# Moteino_Leo.net
KiCad netlist of a schematic drawn in EAGLE
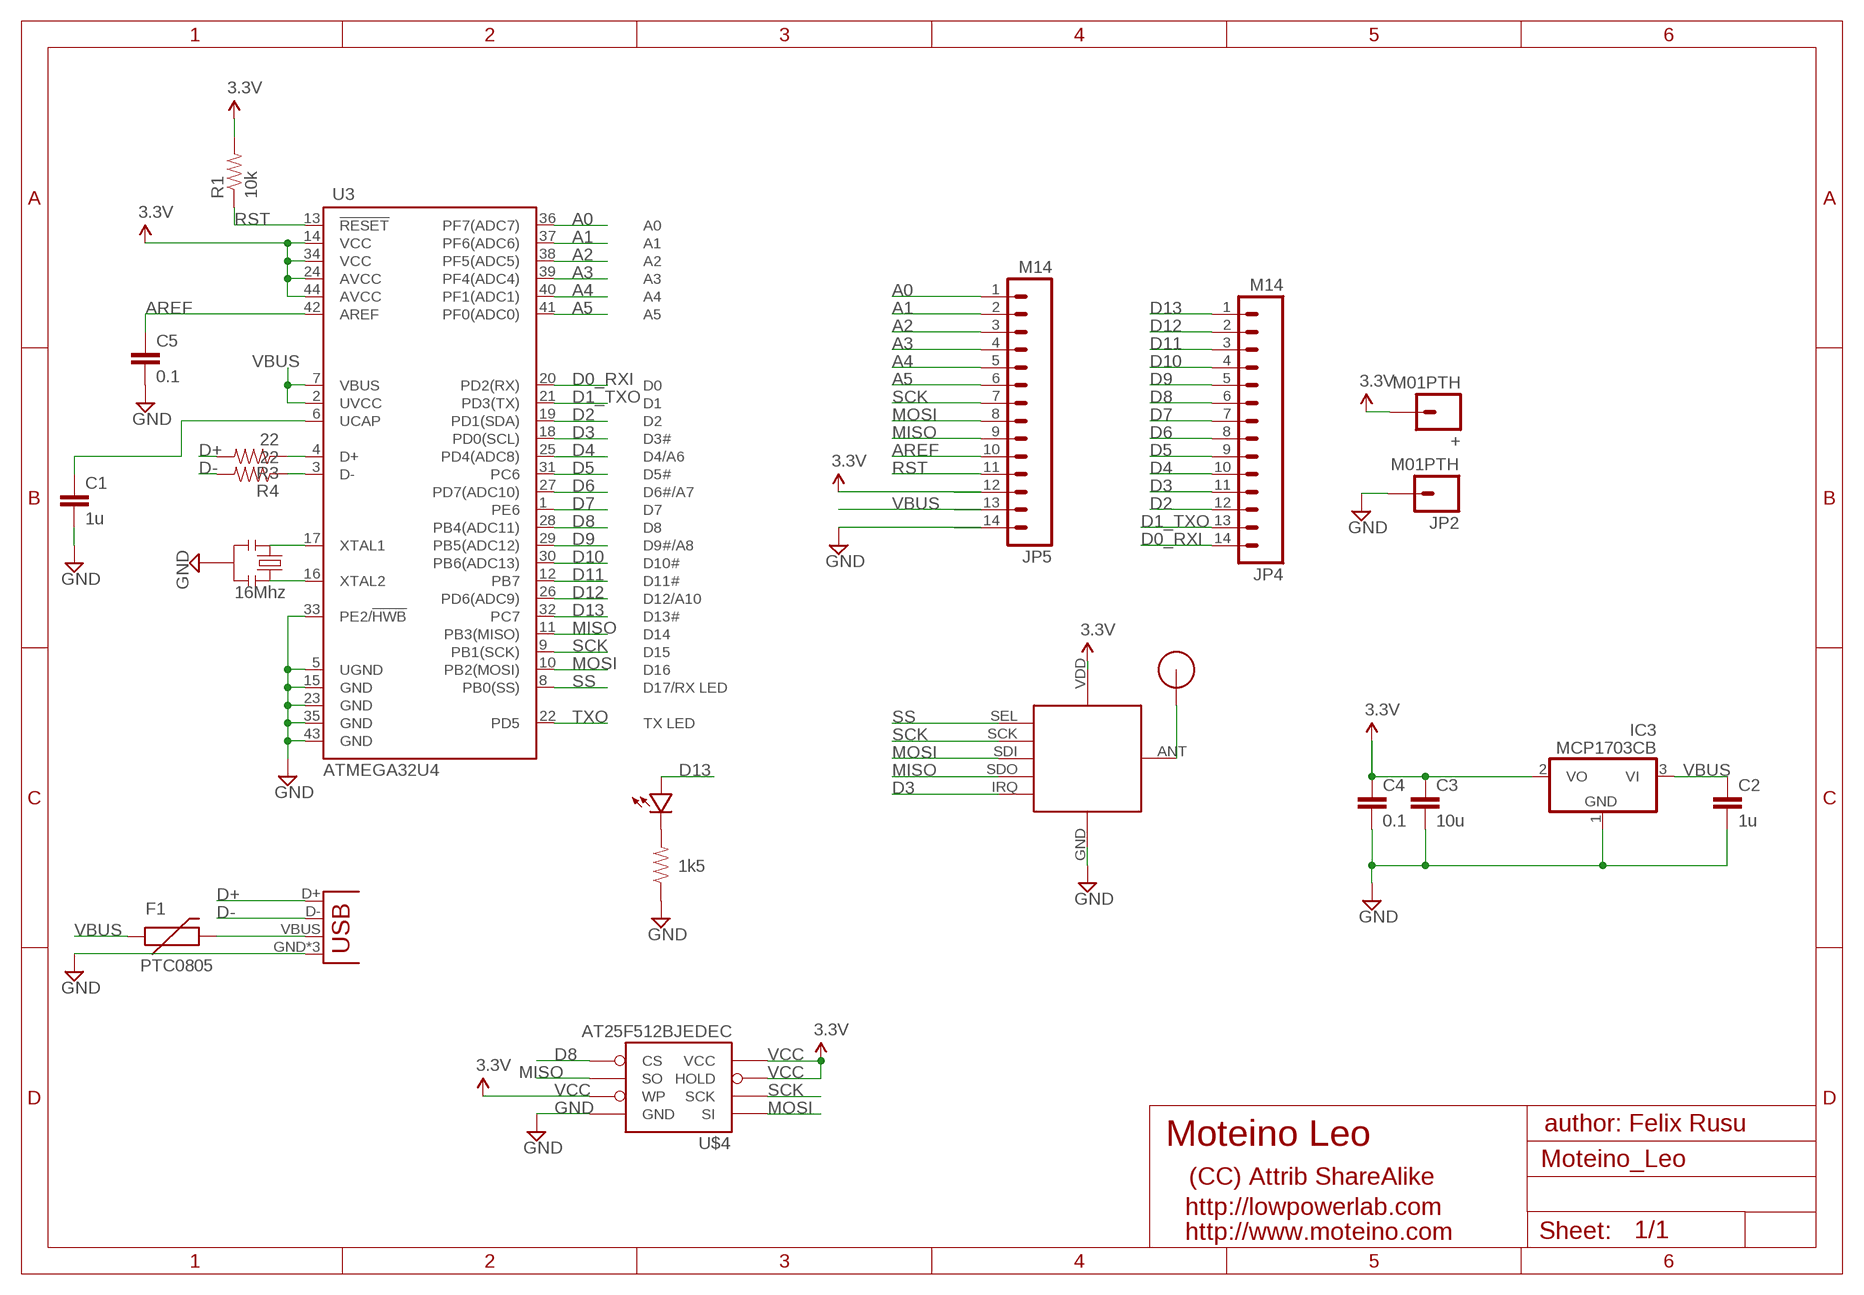
[diagram p0: schematic, sheet 1]

(export (version "E")
  (design (tool "Eeschema 10.0.6"))
  (components
    (comp (ref "+")
      (value "M01PTH")
      (footprint "eagle-import:1X01")
      (libsource (lib "eagle-import") (part "M01PTH"))
    )
    (comp (ref "C1")
      (value "1u")
      (footprint "eagle-import:0603-CAP")
      (libsource (lib "eagle-import") (part "CAP0603-CAP"))
    )
    (comp (ref "C2")
      (value "1u")
      (footprint "eagle-import:0603-CAP")
      (libsource (lib "eagle-import") (part "CAP0603-CAP"))
    )
    (comp (ref "C3")
      (value "10u")
      (footprint "eagle-import:0805-CAP")
      (libsource (lib "eagle-import") (part "CAP0805-CAP"))
    )
    (comp (ref "C4")
      (value "0.1")
      (footprint "eagle-import:0603-CAP")
      (libsource (lib "eagle-import") (part "CAP0603-CAP"))
    )
    (comp (ref "C5")
      (value "0.1")
      (footprint "eagle-import:0603-CAP")
      (libsource (lib "eagle-import") (part "CAP0603-CAP"))
    )
    (comp (ref "F1")
      (value "PTC0805")
      (footprint "eagle-import:0805-PTC")
      (libsource (lib "eagle-import") (part "PTC0805"))
    )
    (comp (ref "IC3")
      (value "MCP1703CB")
      (footprint "eagle-import:SOT23")
      (libsource (lib "eagle-import") (part "MCP1703CB"))
    )
    (comp (ref "JP2")
      (value "M01PTH")
      (footprint "eagle-import:1X01")
      (libsource (lib "eagle-import") (part "M01PTH"))
    )
    (comp (ref "JP3")
      (value "USB-MICROB")
      (footprint "eagle-import:USB-MICROB")
      (libsource (lib "eagle-import") (part "USB-MICROB"))
    )
    (comp (ref "JP4")
      (value "M14")
      (footprint "eagle-import:1X14")
      (libsource (lib "eagle-import") (part "M14"))
    )
    (comp (ref "JP5")
      (value "M14")
      (footprint "eagle-import:1X14")
      (libsource (lib "eagle-import") (part "M14"))
    )
    (comp (ref "R1")
      (value "10k")
      (footprint "eagle-import:0603-RES")
      (libsource (lib "eagle-import") (part "RESISTOR0603-RES"))
    )
    (comp (ref "R2")
      (value "1k5")
      (footprint "eagle-import:0603-RES")
      (libsource (lib "eagle-import") (part "RESISTOR0603-RES"))
    )
    (comp (ref "R3")
      (value "22")
      (footprint "eagle-import:0603-RES")
      (libsource (lib "eagle-import") (part "RESISTOR0603-RES"))
    )
    (comp (ref "R4")
      (value "22")
      (footprint "eagle-import:0603-RES")
      (libsource (lib "eagle-import") (part "RESISTOR0603-RES"))
    )
    (comp (ref "RFM12B")
      (value "RFM12B_MINPADS")
      (footprint "eagle-import:RFM12B-MINPADS")
      (libsource (lib "eagle-import") (part "RFM12B_MINPADS"))
    )
    (comp (ref "U$1")
      (value "RFM12B_ANTENNA")
      (footprint "eagle-import:RFM12B-ANTENNA")
      (libsource (lib "eagle-import") (part "RFM12B_ANTENNA"))
    )
    (comp (ref "U$2")
      (value "LED0603")
      (footprint "eagle-import:0603-LED")
      (libsource (lib "eagle-import") (part "LED0603"))
    )
    (comp (ref "U$4")
      (value "AT25F512BJEDEC")
      (footprint "eagle-import:SO08")
      (libsource (lib "eagle-import") (part "AT25F512BJEDEC"))
    )
    (comp (ref "U3")
      (value "ATMEGA32U4")
      (footprint "eagle-import:QFN-44-NOPAD")
      (libsource (lib "eagle-import") (part "ATMEGA32U4QFN2"))
    )
    (comp (ref "X1")
      (value "16Mhz")
      (footprint "eagle-import:RESONATOR-SMD")
      (libsource (lib "eagle-import") (part "RESONATORSMD"))
    )
  )
  (nets
    (net (code "1") (name "/A0") (class "Default")
      (node (ref "JP5") (pin "1") (pinfunction "1_1") (pintype "passive"))
      (node (ref "U3") (pin "36") (pinfunction "PF7(ADC7)_36") (pintype "bidirectional"))
    )
    (net (code "2") (name "/A1") (class "Default")
      (node (ref "JP5") (pin "2") (pinfunction "2_2") (pintype "passive"))
      (node (ref "U3") (pin "37") (pinfunction "PF6(ADC6)_37") (pintype "bidirectional"))
    )
    (net (code "3") (name "/A2") (class "Default")
      (node (ref "JP5") (pin "3") (pinfunction "3_3") (pintype "passive"))
      (node (ref "U3") (pin "38") (pinfunction "PF5(ADC5)_38") (pintype "bidirectional"))
    )
    (net (code "4") (name "/A3") (class "Default")
      (node (ref "JP5") (pin "4") (pinfunction "4_4") (pintype "passive"))
      (node (ref "U3") (pin "39") (pinfunction "PF4(ADC4)_39") (pintype "bidirectional"))
    )
    (net (code "5") (name "/A4") (class "Default")
      (node (ref "JP5") (pin "5") (pinfunction "5_5") (pintype "passive"))
      (node (ref "U3") (pin "40") (pinfunction "PF1(ADC1)_40") (pintype "bidirectional"))
    )
    (net (code "6") (name "/A5") (class "Default")
      (node (ref "JP5") (pin "6") (pinfunction "6_6") (pintype "passive"))
      (node (ref "U3") (pin "41") (pinfunction "PF0(ADC0)_41") (pintype "bidirectional"))
    )
    (net (code "7") (name "/AREF") (class "Default")
      (node (ref "C5") (pin "1") (pinfunction "1_1") (pintype "passive"))
      (node (ref "JP5") (pin "10") (pinfunction "10_10") (pintype "passive"))
      (node (ref "U3") (pin "42") (pinfunction "AREF_42") (pintype "bidirectional"))
    )
    (net (code "8") (name "/D+") (class "Default")
      (node (ref "JP3") (pin "D+") (pinfunction "D+_D+") (pintype "bidirectional"))
      (node (ref "R3") (pin "2") (pinfunction "2_2") (pintype "passive"))
    )
    (net (code "9") (name "/D-") (class "Default")
      (node (ref "JP3") (pin "D-") (pinfunction "D-_D-") (pintype "bidirectional"))
      (node (ref "R4") (pin "2") (pinfunction "2_2") (pintype "passive"))
    )
    (net (code "10") (name "/D0_RXI") (class "Default")
      (node (ref "JP4") (pin "14") (pinfunction "14_14") (pintype "passive"))
      (node (ref "U3") (pin "20") (pinfunction "PD2(RX)_20") (pintype "bidirectional"))
    )
    (net (code "11") (name "/D1_TXO") (class "Default")
      (node (ref "JP4") (pin "13") (pinfunction "13_13") (pintype "passive"))
      (node (ref "U3") (pin "21") (pinfunction "PD3(TX)_21") (pintype "bidirectional"))
    )
    (net (code "12") (name "/D2") (class "Default")
      (node (ref "JP4") (pin "12") (pinfunction "12_12") (pintype "passive"))
      (node (ref "U3") (pin "19") (pinfunction "PD1(SDA)_19") (pintype "bidirectional"))
    )
    (net (code "13") (name "/D3") (class "Default")
      (node (ref "JP4") (pin "11") (pinfunction "11_11") (pintype "passive"))
      (node (ref "RFM12B") (pin "IRQ") (pinfunction "IRQ_IRQ") (pintype "bidirectional"))
      (node (ref "U3") (pin "18") (pinfunction "PD0(SCL)_18") (pintype "bidirectional"))
    )
    (net (code "14") (name "/D4") (class "Default")
      (node (ref "JP4") (pin "10") (pinfunction "10_10") (pintype "passive"))
      (node (ref "U3") (pin "25") (pinfunction "PD4(ADC8)_25") (pintype "bidirectional"))
    )
    (net (code "15") (name "/D5") (class "Default")
      (node (ref "JP4") (pin "9") (pinfunction "9_9") (pintype "passive"))
      (node (ref "U3") (pin "31") (pinfunction "PC6_31") (pintype "bidirectional"))
    )
    (net (code "16") (name "/D6") (class "Default")
      (node (ref "JP4") (pin "8") (pinfunction "8_8") (pintype "passive"))
      (node (ref "U3") (pin "27") (pinfunction "PD7(ADC10)_27") (pintype "bidirectional"))
    )
    (net (code "17") (name "/D7") (class "Default")
      (node (ref "JP4") (pin "7") (pinfunction "7_7") (pintype "passive"))
      (node (ref "U3") (pin "1") (pinfunction "PE6_1") (pintype "bidirectional"))
    )
    (net (code "18") (name "/D8") (class "Default")
      (node (ref "JP4") (pin "6") (pinfunction "6_6") (pintype "passive"))
      (node (ref "U$4") (pin "1_CS") (pinfunction "CS_1_CS") (pintype "bidirectional"))
      (node (ref "U3") (pin "28") (pinfunction "PB4(ADC11)_28") (pintype "bidirectional"))
    )
    (net (code "19") (name "/D9") (class "Default")
      (node (ref "JP4") (pin "5") (pinfunction "5_5") (pintype "passive"))
      (node (ref "U3") (pin "29") (pinfunction "PB5(ADC12)_29") (pintype "bidirectional"))
    )
    (net (code "20") (name "/D10") (class "Default")
      (node (ref "JP4") (pin "4") (pinfunction "4_4") (pintype "passive"))
      (node (ref "U3") (pin "30") (pinfunction "PB6(ADC13)_30") (pintype "bidirectional"))
    )
    (net (code "21") (name "/D11") (class "Default")
      (node (ref "JP4") (pin "3") (pinfunction "3_3") (pintype "passive"))
      (node (ref "U3") (pin "12") (pinfunction "PB7_12") (pintype "bidirectional"))
    )
    (net (code "22") (name "/D12") (class "Default")
      (node (ref "JP4") (pin "2") (pinfunction "2_2") (pintype "passive"))
      (node (ref "U3") (pin "26") (pinfunction "PD6(ADC9)_26") (pintype "bidirectional"))
    )
    (net (code "23") (name "/D13") (class "Default")
      (node (ref "JP4") (pin "1") (pinfunction "1_1") (pintype "passive"))
      (node (ref "U$2") (pin "PLUS") (pinfunction "PLUS_PLUS") (pintype "passive"))
      (node (ref "U3") (pin "32") (pinfunction "PC7_32") (pintype "bidirectional"))
    )
    (net (code "24") (name "/MISO") (class "Default")
      (node (ref "JP5") (pin "9") (pinfunction "9_9") (pintype "passive"))
      (node (ref "RFM12B") (pin "SDO") (pinfunction "SDO/MISO_SDO") (pintype "bidirectional"))
      (node (ref "U$4") (pin "2_SO") (pinfunction "SO_2_SO") (pintype "bidirectional"))
      (node (ref "U3") (pin "11") (pinfunction "PB3(MISO)_11") (pintype "bidirectional"))
    )
    (net (code "25") (name "/MOSI") (class "Default")
      (node (ref "JP5") (pin "8") (pinfunction "8_8") (pintype "passive"))
      (node (ref "RFM12B") (pin "SDI") (pinfunction "SDI/MOSI_SDI") (pintype "bidirectional"))
      (node (ref "U$4") (pin "5_SI") (pinfunction "SI_5_SI") (pintype "bidirectional"))
      (node (ref "U3") (pin "10") (pinfunction "PB2(MOSI)_10") (pintype "bidirectional"))
    )
    (net (code "26") (name "/RST") (class "Default")
      (node (ref "JP5") (pin "11") (pinfunction "11_11") (pintype "passive"))
      (node (ref "R1") (pin "1") (pinfunction "1_1") (pintype "passive"))
      (node (ref "U3") (pin "13") (pinfunction "~{RESET}_13") (pintype "bidirectional"))
    )
    (net (code "27") (name "/SCK") (class "Default")
      (node (ref "JP5") (pin "7") (pinfunction "7_7") (pintype "passive"))
      (node (ref "RFM12B") (pin "SCK") (pinfunction "SCK_SCK") (pintype "bidirectional"))
      (node (ref "U$4") (pin "6_SCK") (pinfunction "SCK_6_SCK") (pintype "bidirectional"))
      (node (ref "U3") (pin "9") (pinfunction "PB1(SCK)_9") (pintype "bidirectional"))
    )
    (net (code "28") (name "/SS") (class "Default")
      (node (ref "RFM12B") (pin "SEL") (pinfunction "SEL_SEL") (pintype "bidirectional"))
      (node (ref "U3") (pin "8") (pinfunction "PB0(SS)_8") (pintype "bidirectional"))
    )
    (net (code "29") (name "/TXO") (class "Default")
      (node (ref "U3") (pin "22") (pinfunction "PD5_22") (pintype "bidirectional"))
    )
    (net (code "30") (name "/VBUS") (class "Default")
      (node (ref "C2") (pin "1") (pinfunction "1_1") (pintype "passive"))
      (node (ref "F1") (pin "1") (pinfunction "1_1") (pintype "bidirectional"))
      (node (ref "IC3") (pin "3") (pinfunction "VI_3") (pintype "input"))
      (node (ref "JP5") (pin "13") (pinfunction "13_13") (pintype "passive"))
      (node (ref "U3") (pin "2") (pinfunction "UVCC_2") (pintype "bidirectional"))
      (node (ref "U3") (pin "7") (pinfunction "VBUS_7") (pintype "bidirectional"))
    )
    (net (code "31") (name "3.3V") (class "Default")
      (node (ref "+") (pin "1") (pinfunction "1_1") (pintype "passive"))
      (node (ref "C3") (pin "1") (pinfunction "1_1") (pintype "passive"))
      (node (ref "C4") (pin "1") (pinfunction "1_1") (pintype "passive"))
      (node (ref "IC3") (pin "2") (pinfunction "VO_2") (pintype "passive"))
      (node (ref "JP5") (pin "12") (pinfunction "12_12") (pintype "passive"))
      (node (ref "R1") (pin "2") (pinfunction "2_2") (pintype "passive"))
      (node (ref "RFM12B") (pin "VDD") (pinfunction "VDD_VDD") (pintype "bidirectional"))
      (node (ref "U$4") (pin "3_WP") (pinfunction "WP_3_WP") (pintype "bidirectional"))
      (node (ref "U$4") (pin "7_HOLD") (pinfunction "HOLD_7_HOLD") (pintype "bidirectional"))
      (node (ref "U$4") (pin "8_VCC") (pinfunction "VCC_8_VCC") (pintype "bidirectional"))
      (node (ref "U3") (pin "14") (pinfunction "VCC_14") (pintype "bidirectional"))
      (node (ref "U3") (pin "24") (pinfunction "AVCC_24") (pintype "bidirectional"))
      (node (ref "U3") (pin "34") (pinfunction "VCC_34") (pintype "bidirectional"))
      (node (ref "U3") (pin "44") (pinfunction "AVCC_44") (pintype "bidirectional"))
    )
    (net (code "32") (name "GND") (class "Default")
      (node (ref "C1") (pin "2") (pinfunction "2_2") (pintype "passive"))
      (node (ref "C2") (pin "2") (pinfunction "2_2") (pintype "passive"))
      (node (ref "C3") (pin "2") (pinfunction "2_2") (pintype "passive"))
      (node (ref "C4") (pin "2") (pinfunction "2_2") (pintype "passive"))
      (node (ref "C5") (pin "2") (pinfunction "2_2") (pintype "passive"))
      (node (ref "IC3") (pin "1") (pinfunction "GND_1") (pintype "passive"))
      (node (ref "JP2") (pin "1") (pinfunction "1_1") (pintype "passive"))
      (node (ref "JP3") (pin "GND") (pinfunction "GND_GND") (pintype "bidirectional"))
      (node (ref "JP3") (pin "MT1") (pinfunction "GND_MT1") (pintype "bidirectional"))
      (node (ref "JP3") (pin "MT2") (pinfunction "GND_MT2") (pintype "bidirectional"))
      (node (ref "JP5") (pin "14") (pinfunction "14_14") (pintype "passive"))
      (node (ref "R2") (pin "1") (pinfunction "1_1") (pintype "passive"))
      (node (ref "RFM12B") (pin "GND") (pinfunction "GND_GND") (pintype "bidirectional"))
      (node (ref "U$4") (pin "4_GND") (pinfunction "GND_4_GND") (pintype "bidirectional"))
      (node (ref "U3") (pin "15") (pinfunction "GND_15") (pintype "bidirectional"))
      (node (ref "U3") (pin "23") (pinfunction "GND_23") (pintype "bidirectional"))
      (node (ref "U3") (pin "33") (pinfunction "PE2/~{HWB}_33") (pintype "bidirectional"))
      (node (ref "U3") (pin "35") (pinfunction "GND_35") (pintype "bidirectional"))
      (node (ref "U3") (pin "43") (pinfunction "GND_43") (pintype "bidirectional"))
      (node (ref "U3") (pin "5") (pinfunction "UGND_5") (pintype "bidirectional"))
      (node (ref "X1") (pin "2") (pinfunction "2_2") (pintype "passive"))
    )
    (net (code "33") (name "Net-(F1-Pad2)") (class "Default")
      (node (ref "F1") (pin "2") (pinfunction "2_2") (pintype "bidirectional"))
      (node (ref "JP3") (pin "VBUS") (pinfunction "VBUS_VBUS") (pintype "bidirectional"))
    )
    (net (code "34") (name "Net-(R2-Pad2)") (class "Default")
      (node (ref "R2") (pin "2") (pinfunction "2_2") (pintype "passive"))
      (node (ref "U$2") (pin "MINUS") (pinfunction "MINUS_MINUS") (pintype "passive"))
    )
    (net (code "35") (name "Net-(U$1-1)") (class "Default")
      (node (ref "RFM12B") (pin "ANT") (pinfunction "ANT_ANT") (pintype "bidirectional"))
      (node (ref "U$1") (pin "P$1") (pinfunction "1_P$1") (pintype "bidirectional"))
    )
    (net (code "36") (name "Net-(U3-D+)") (class "Default")
      (node (ref "R3") (pin "1") (pinfunction "1_1") (pintype "passive"))
      (node (ref "U3") (pin "4") (pinfunction "D+_4") (pintype "bidirectional"))
    )
    (net (code "37") (name "Net-(U3-D-)") (class "Default")
      (node (ref "R4") (pin "1") (pinfunction "1_1") (pintype "passive"))
      (node (ref "U3") (pin "3") (pinfunction "D-_3") (pintype "bidirectional"))
    )
    (net (code "38") (name "Net-(U3-UCAP)") (class "Default")
      (node (ref "C1") (pin "1") (pinfunction "1_1") (pintype "passive"))
      (node (ref "U3") (pin "6") (pinfunction "UCAP_6") (pintype "bidirectional"))
    )
    (net (code "39") (name "Net-(U3-XTAL1)") (class "Default")
      (node (ref "U3") (pin "17") (pinfunction "XTAL1_17") (pintype "bidirectional"))
      (node (ref "X1") (pin "1") (pinfunction "1_1") (pintype "passive"))
    )
    (net (code "40") (name "Net-(U3-XTAL2)") (class "Default")
      (node (ref "U3") (pin "16") (pinfunction "XTAL2_16") (pintype "bidirectional"))
      (node (ref "X1") (pin "3") (pinfunction "3_3") (pintype "passive"))
    )
  )
)
